# b_pubsub_lower_bore_isolate_5V.net
KiCad netlist of a schematic drawn in EAGLE
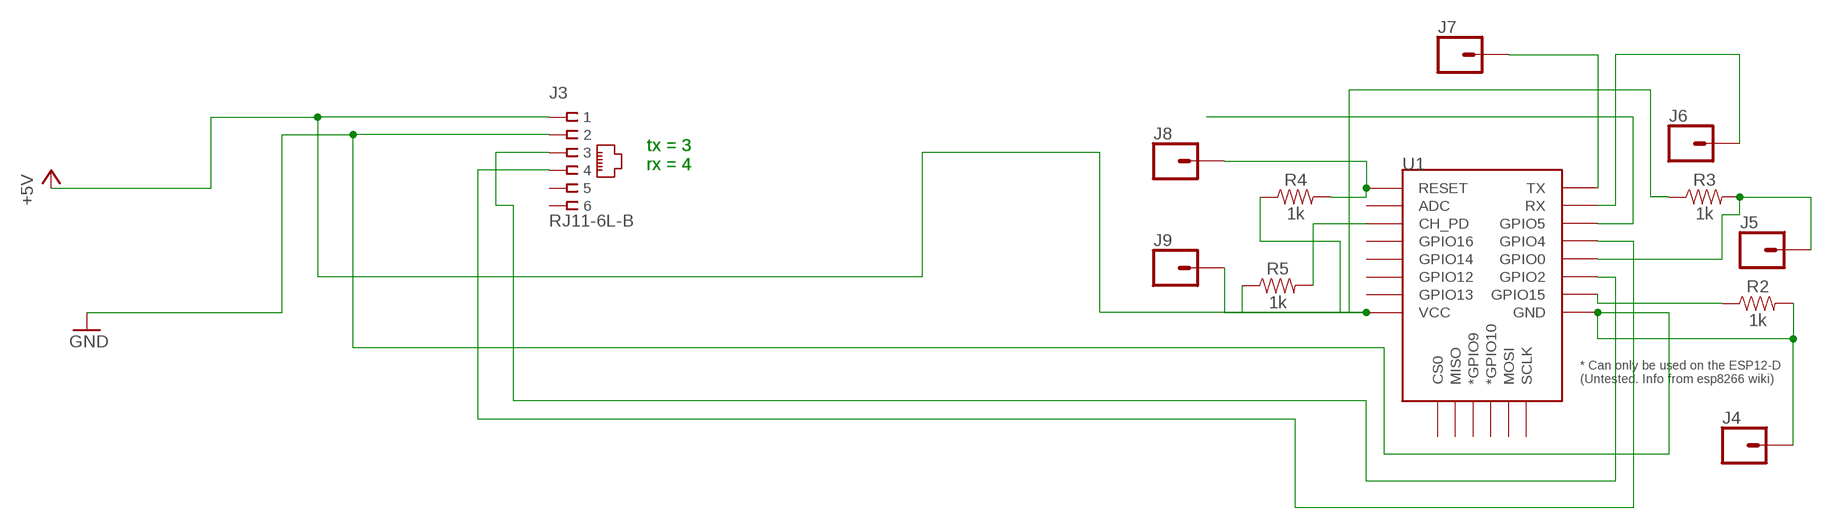
[diagram p0: schematic, sheet 1]

(export (version "E")
  (design (tool "Eeschema 10.0.6"))
  (components
    (comp (ref "J3")
      (value "RJ11-6L-B")
      (footprint "eagle-import:RJ11-NO_SHIELD")
      (fields (field (name "MF") "TYCO ELECTRONICS"))
      (libsource (lib "eagle-import") (part "RJ11-6L-B"))
    )
    (comp (ref "J4")
      (value "CONN_01")
      (footprint "eagle-import:1X01")
      (libsource (lib "eagle-import") (part "CONN_01"))
    )
    (comp (ref "J5")
      (value "CONN_01")
      (footprint "eagle-import:1X01")
      (libsource (lib "eagle-import") (part "CONN_01"))
    )
    (comp (ref "J6")
      (value "CONN_01")
      (footprint "eagle-import:1X01")
      (libsource (lib "eagle-import") (part "CONN_01"))
    )
    (comp (ref "J7")
      (value "CONN_01")
      (footprint "eagle-import:1X01")
      (libsource (lib "eagle-import") (part "CONN_01"))
    )
    (comp (ref "J8")
      (value "CONN_01")
      (footprint "eagle-import:1X01")
      (libsource (lib "eagle-import") (part "CONN_01"))
    )
    (comp (ref "J9")
      (value "CONN_01")
      (footprint "eagle-import:1X01")
      (libsource (lib "eagle-import") (part "CONN_01"))
    )
    (comp (ref "R2")
      (value "1k")
      (footprint "eagle-import:AXIAL-0.3")
      (libsource (lib "eagle-import") (part "1KOHM-HORIZ-1/4W-1%"))
    )
    (comp (ref "R3")
      (value "1k")
      (footprint "eagle-import:AXIAL-0.3")
      (libsource (lib "eagle-import") (part "1KOHM-HORIZ-1/4W-1%"))
    )
    (comp (ref "R4")
      (value "1k")
      (footprint "eagle-import:AXIAL-0.3")
      (libsource (lib "eagle-import") (part "1KOHM-HORIZ-1/4W-1%"))
    )
    (comp (ref "R5")
      (value "1k")
      (footprint "eagle-import:AXIAL-0.3")
      (libsource (lib "eagle-import") (part "1KOHM-HORIZ-1/4W-1%"))
    )
    (comp (ref "U1")
      (value "ESP12ESMD")
      (footprint "eagle-import:ESP12E-SMD")
      (libsource (lib "eagle-import") (part "ESP12ESMD"))
    )
  )
  (nets
    (net (code "1") (name "+5V") (class "Default")
      (node (ref "J3") (pin "1") (pinfunction "1_1") (pintype "passive"))
      (node (ref "J9") (pin "1") (pinfunction "1_1") (pintype "passive"))
      (node (ref "R3") (pin "P$1") (pinfunction "1_P$1") (pintype "passive"))
      (node (ref "R4") (pin "P$1") (pinfunction "1_P$1") (pintype "passive"))
      (node (ref "R5") (pin "P$1") (pinfunction "1_P$1") (pintype "passive"))
      (node (ref "U1") (pin "VCC") (pinfunction "VCC_VCC") (pintype "bidirectional"))
    )
    (net (code "2") (name "GND") (class "Default")
      (node (ref "J3") (pin "2") (pinfunction "2_2") (pintype "passive"))
      (node (ref "J4") (pin "1") (pinfunction "1_1") (pintype "passive"))
      (node (ref "R2") (pin "P$2") (pinfunction "2_P$2") (pintype "passive"))
      (node (ref "U1") (pin "GND") (pinfunction "GND_GND") (pintype "bidirectional"))
    )
    (net (code "3") (name "Net-(J3-Pad3)") (class "Default")
      (node (ref "J3") (pin "3") (pinfunction "3_3") (pintype "passive"))
      (node (ref "U1") (pin "GPIO2") (pinfunction "GPIO2_GPIO2") (pintype "bidirectional"))
    )
    (net (code "4") (name "Net-(J3-Pad4)") (class "Default")
      (node (ref "J3") (pin "4") (pinfunction "4_4") (pintype "passive"))
      (node (ref "U1") (pin "GPIO4") (pinfunction "GPIO4_GPIO4") (pintype "bidirectional"))
    )
    (net (code "5") (name "Net-(R2-1)") (class "Default")
      (node (ref "R2") (pin "P$1") (pinfunction "1_P$1") (pintype "passive"))
      (node (ref "U1") (pin "GPIO15") (pinfunction "GPIO15_GPIO15") (pintype "bidirectional"))
    )
    (net (code "6") (name "Net-(R3-2)") (class "Default")
      (node (ref "J5") (pin "1") (pinfunction "1_1") (pintype "passive"))
      (node (ref "R3") (pin "P$2") (pinfunction "2_P$2") (pintype "passive"))
      (node (ref "U1") (pin "GPIO0") (pinfunction "GPIO0_GPIO0") (pintype "bidirectional"))
    )
    (net (code "7") (name "Net-(R4-2)") (class "Default")
      (node (ref "J8") (pin "1") (pinfunction "1_1") (pintype "passive"))
      (node (ref "R4") (pin "P$2") (pinfunction "2_P$2") (pintype "passive"))
      (node (ref "U1") (pin "RESET") (pinfunction "RESET_RESET") (pintype "bidirectional"))
    )
    (net (code "8") (name "Net-(R5-2)") (class "Default")
      (node (ref "R5") (pin "P$2") (pinfunction "2_P$2") (pintype "passive"))
      (node (ref "U1") (pin "CH_PD") (pinfunction "CH_PD_CH_PD") (pintype "bidirectional"))
    )
    (net (code "9") (name "Net-(U1-RX)") (class "Default")
      (node (ref "J6") (pin "1") (pinfunction "1_1") (pintype "passive"))
      (node (ref "U1") (pin "RXD0") (pinfunction "RX_RXD0") (pintype "bidirectional"))
    )
    (net (code "10") (name "Net-(U1-TX)") (class "Default")
      (node (ref "J7") (pin "1") (pinfunction "1_1") (pintype "passive"))
      (node (ref "U1") (pin "TXD0") (pinfunction "TX_TXD0") (pintype "bidirectional"))
    )
    (net (code "11") (name "unconnected-(J3-Pad5)") (class "Default")
      (node (ref "J3") (pin "5") (pinfunction "5_5") (pintype "passive"))
    )
    (net (code "12") (name "unconnected-(J3-Pad6)") (class "Default")
      (node (ref "J3") (pin "6") (pinfunction "6_6") (pintype "passive"))
    )
    (net (code "13") (name "unconnected-(U1-*GPIO9-PadGPIO9)") (class "Default")
      (node (ref "U1") (pin "GPIO9") (pinfunction "*GPIO9_GPIO9") (pintype "bidirectional"))
    )
    (net (code "14") (name "unconnected-(U1-*GPIO10-PadGPIO10)") (class "Default")
      (node (ref "U1") (pin "GPIO10") (pinfunction "*GPIO10_GPIO10") (pintype "bidirectional"))
    )
    (net (code "15") (name "unconnected-(U1-PadADC)") (class "Default")
      (node (ref "U1") (pin "ADC") (pinfunction "ADC_ADC") (pintype "bidirectional"))
    )
    (net (code "16") (name "unconnected-(U1-PadCS0)") (class "Default")
      (node (ref "U1") (pin "CS0") (pinfunction "CS0_CS0") (pintype "bidirectional"))
    )
    (net (code "17") (name "unconnected-(U1-PadGPIO5)") (class "Default")
      (node (ref "U1") (pin "GPIO5") (pinfunction "GPIO5_GPIO5") (pintype "bidirectional"))
    )
    (net (code "18") (name "unconnected-(U1-PadGPIO12)") (class "Default")
      (node (ref "U1") (pin "GPIO12") (pinfunction "GPIO12_GPIO12") (pintype "bidirectional"))
    )
    (net (code "19") (name "unconnected-(U1-PadGPIO13)") (class "Default")
      (node (ref "U1") (pin "GPIO13") (pinfunction "GPIO13_GPIO13") (pintype "bidirectional"))
    )
    (net (code "20") (name "unconnected-(U1-PadGPIO14)") (class "Default")
      (node (ref "U1") (pin "GPIO14") (pinfunction "GPIO14_GPIO14") (pintype "bidirectional"))
    )
    (net (code "21") (name "unconnected-(U1-PadGPIO16)") (class "Default")
      (node (ref "U1") (pin "GPIO16") (pinfunction "GPIO16_GPIO16") (pintype "bidirectional"))
    )
    (net (code "22") (name "unconnected-(U1-PadMISO)") (class "Default")
      (node (ref "U1") (pin "MISO") (pinfunction "MISO_MISO") (pintype "bidirectional"))
    )
    (net (code "23") (name "unconnected-(U1-PadMOSI)") (class "Default")
      (node (ref "U1") (pin "MOSI") (pinfunction "MOSI_MOSI") (pintype "bidirectional"))
    )
    (net (code "24") (name "unconnected-(U1-PadSCLK)") (class "Default")
      (node (ref "U1") (pin "SCLK") (pinfunction "SCLK_SCLK") (pintype "bidirectional"))
    )
  )
)
